# Adafruit_INA169_CurPowerMonitor.net
KiCad netlist of a schematic drawn in EAGLE
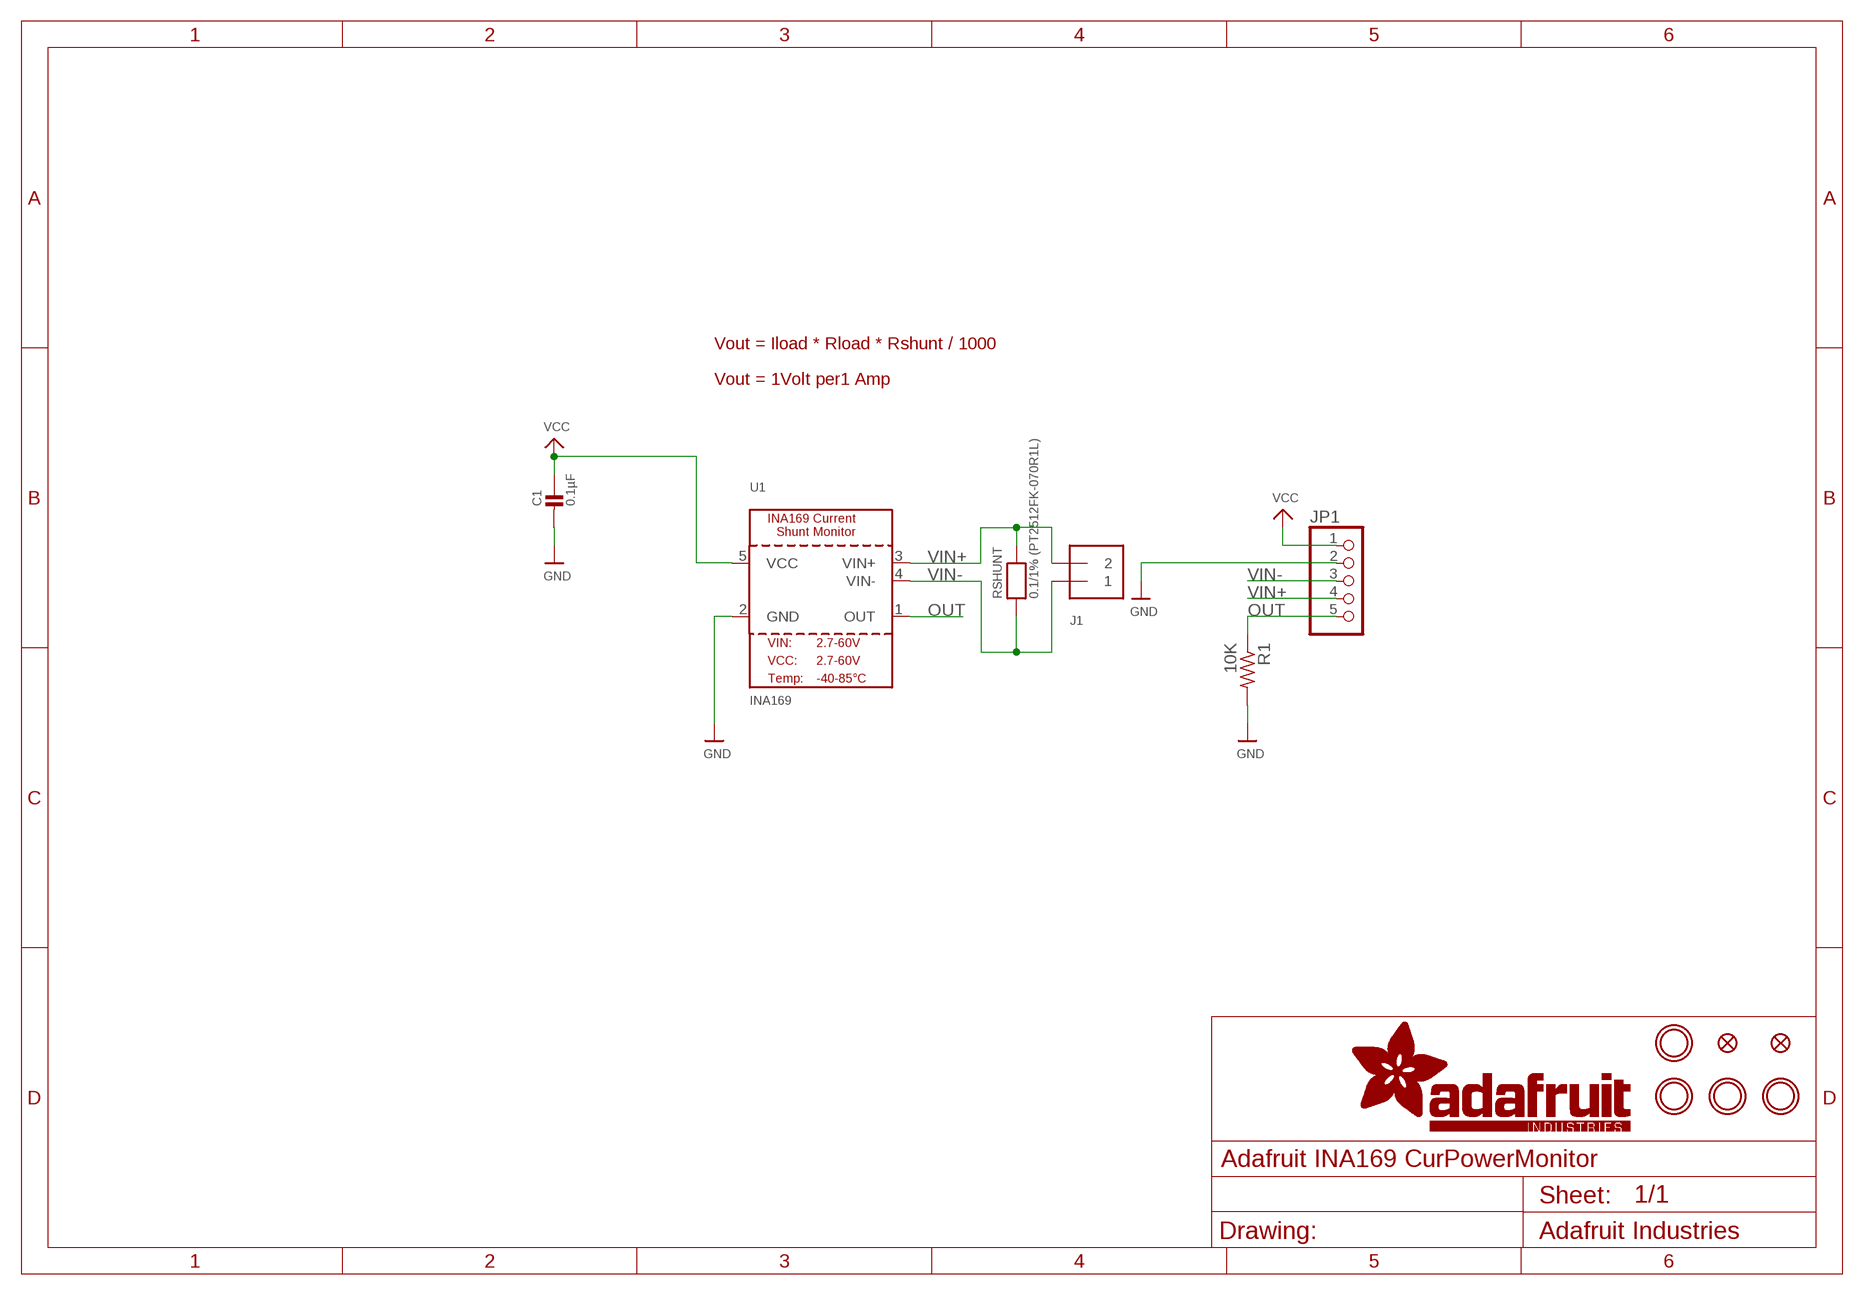
[diagram p0: schematic, sheet 1]

(export (version "E")
  (design (tool "Eeschema 10.0.6"))
  (components
    (comp (ref "C1")
      (value "0.1µF")
      (footprint "eagle-import:0805")
      (libsource (lib "eagle-import") (part "CAP_CERAMIC0805"))
    )
    (comp (ref "FID1")
      (value "FIDUCIAL\"\"")
      (footprint "eagle-import:FIDUCIAL_1MM")
      (libsource (lib "eagle-import") (part "FIDUCIAL{dblquote}{dblquote}"))
    )
    (comp (ref "FID2")
      (value "FIDUCIAL\"\"")
      (footprint "eagle-import:FIDUCIAL_1MM")
      (libsource (lib "eagle-import") (part "FIDUCIAL{dblquote}{dblquote}"))
    )
    (comp (ref "J1")
      (value "TERMBLOCK_1X2")
      (footprint "eagle-import:TERMBLOCK_1X2-3.5MM")
      (libsource (lib "eagle-import") (part "TERMBLOCK_1X2"))
    )
    (comp (ref "JP1")
      (value "HEADER-1X570MIL")
      (footprint "eagle-import:1X05_ROUND_70")
      (libsource (lib "eagle-import") (part "HEADER-1X570MIL"))
    )
    (comp (ref "R1")
      (value "10K")
      (footprint "eagle-import:0805-THM")
      (libsource (lib "eagle-import") (part "RESISTOR_DUAL"))
    )
    (comp (ref "RSHUNT")
      (value "0.1/1% (PT2512FK-070R1L)")
      (footprint "eagle-import:2512")
      (libsource (lib "eagle-import") (part "RESISTOR2512"))
    )
    (comp (ref "U$7")
      (value "MOUNTINGHOLE2.5")
      (footprint "eagle-import:MOUNTINGHOLE_2.5_PLATED")
      (libsource (lib "eagle-import") (part "MOUNTINGHOLE2.5"))
    )
    (comp (ref "U$8")
      (value "MOUNTINGHOLE2.5")
      (footprint "eagle-import:MOUNTINGHOLE_2.5_PLATED")
      (libsource (lib "eagle-import") (part "MOUNTINGHOLE2.5"))
    )
    (comp (ref "U$9")
      (value "MOUNTINGHOLE2.5")
      (footprint "eagle-import:MOUNTINGHOLE_2.5_PLATED")
      (libsource (lib "eagle-import") (part "MOUNTINGHOLE2.5"))
    )
    (comp (ref "U$10")
      (value "MOUNTINGHOLE2.5")
      (footprint "eagle-import:MOUNTINGHOLE_2.5_PLATED")
      (libsource (lib "eagle-import") (part "MOUNTINGHOLE2.5"))
    )
    (comp (ref "U1")
      (value "INA169")
      (footprint "eagle-import:SOT23-5")
      (libsource (lib "eagle-import") (part "INA169"))
    )
  )
  (nets
    (net (code "1") (name "/OUT") (class "Default")
      (node (ref "JP1") (pin "5") (pinfunction "5_5") (pintype "passive"))
      (node (ref "R1") (pin "1") (pinfunction "1_1") (pintype "passive"))
      (node (ref "U1") (pin "1") (pinfunction "OUT_1") (pintype "output"))
    )
    (net (code "2") (name "/VIN+") (class "Default")
      (node (ref "J1") (pin "2") (pinfunction "2_2") (pintype "passive"))
      (node (ref "JP1") (pin "4") (pinfunction "4_4") (pintype "passive"))
      (node (ref "RSHUNT") (pin "2") (pinfunction "2_2") (pintype "passive"))
      (node (ref "U1") (pin "3") (pinfunction "VIN+_3") (pintype "bidirectional"))
    )
    (net (code "3") (name "/VIN-") (class "Default")
      (node (ref "J1") (pin "1") (pinfunction "1_1") (pintype "passive"))
      (node (ref "JP1") (pin "3") (pinfunction "3_3") (pintype "passive"))
      (node (ref "RSHUNT") (pin "1") (pinfunction "1_1") (pintype "passive"))
      (node (ref "U1") (pin "4") (pinfunction "VIN-_4") (pintype "bidirectional"))
    )
    (net (code "4") (name "GND") (class "Default")
      (node (ref "C1") (pin "2") (pinfunction "2_2") (pintype "passive"))
      (node (ref "JP1") (pin "2") (pinfunction "2_2") (pintype "passive"))
      (node (ref "R1") (pin "2") (pinfunction "2_2") (pintype "passive"))
      (node (ref "U1") (pin "2") (pinfunction "GND_2") (pintype "power_in"))
    )
    (net (code "5") (name "VCC") (class "Default")
      (node (ref "C1") (pin "1") (pinfunction "1_1") (pintype "passive"))
      (node (ref "JP1") (pin "1") (pinfunction "1_1") (pintype "passive"))
      (node (ref "U1") (pin "5") (pinfunction "VCC_5") (pintype "power_in"))
    )
  )
)
